# USB_Serial_Quad.net
KiCad netlist of a schematic drawn in Altium Designer
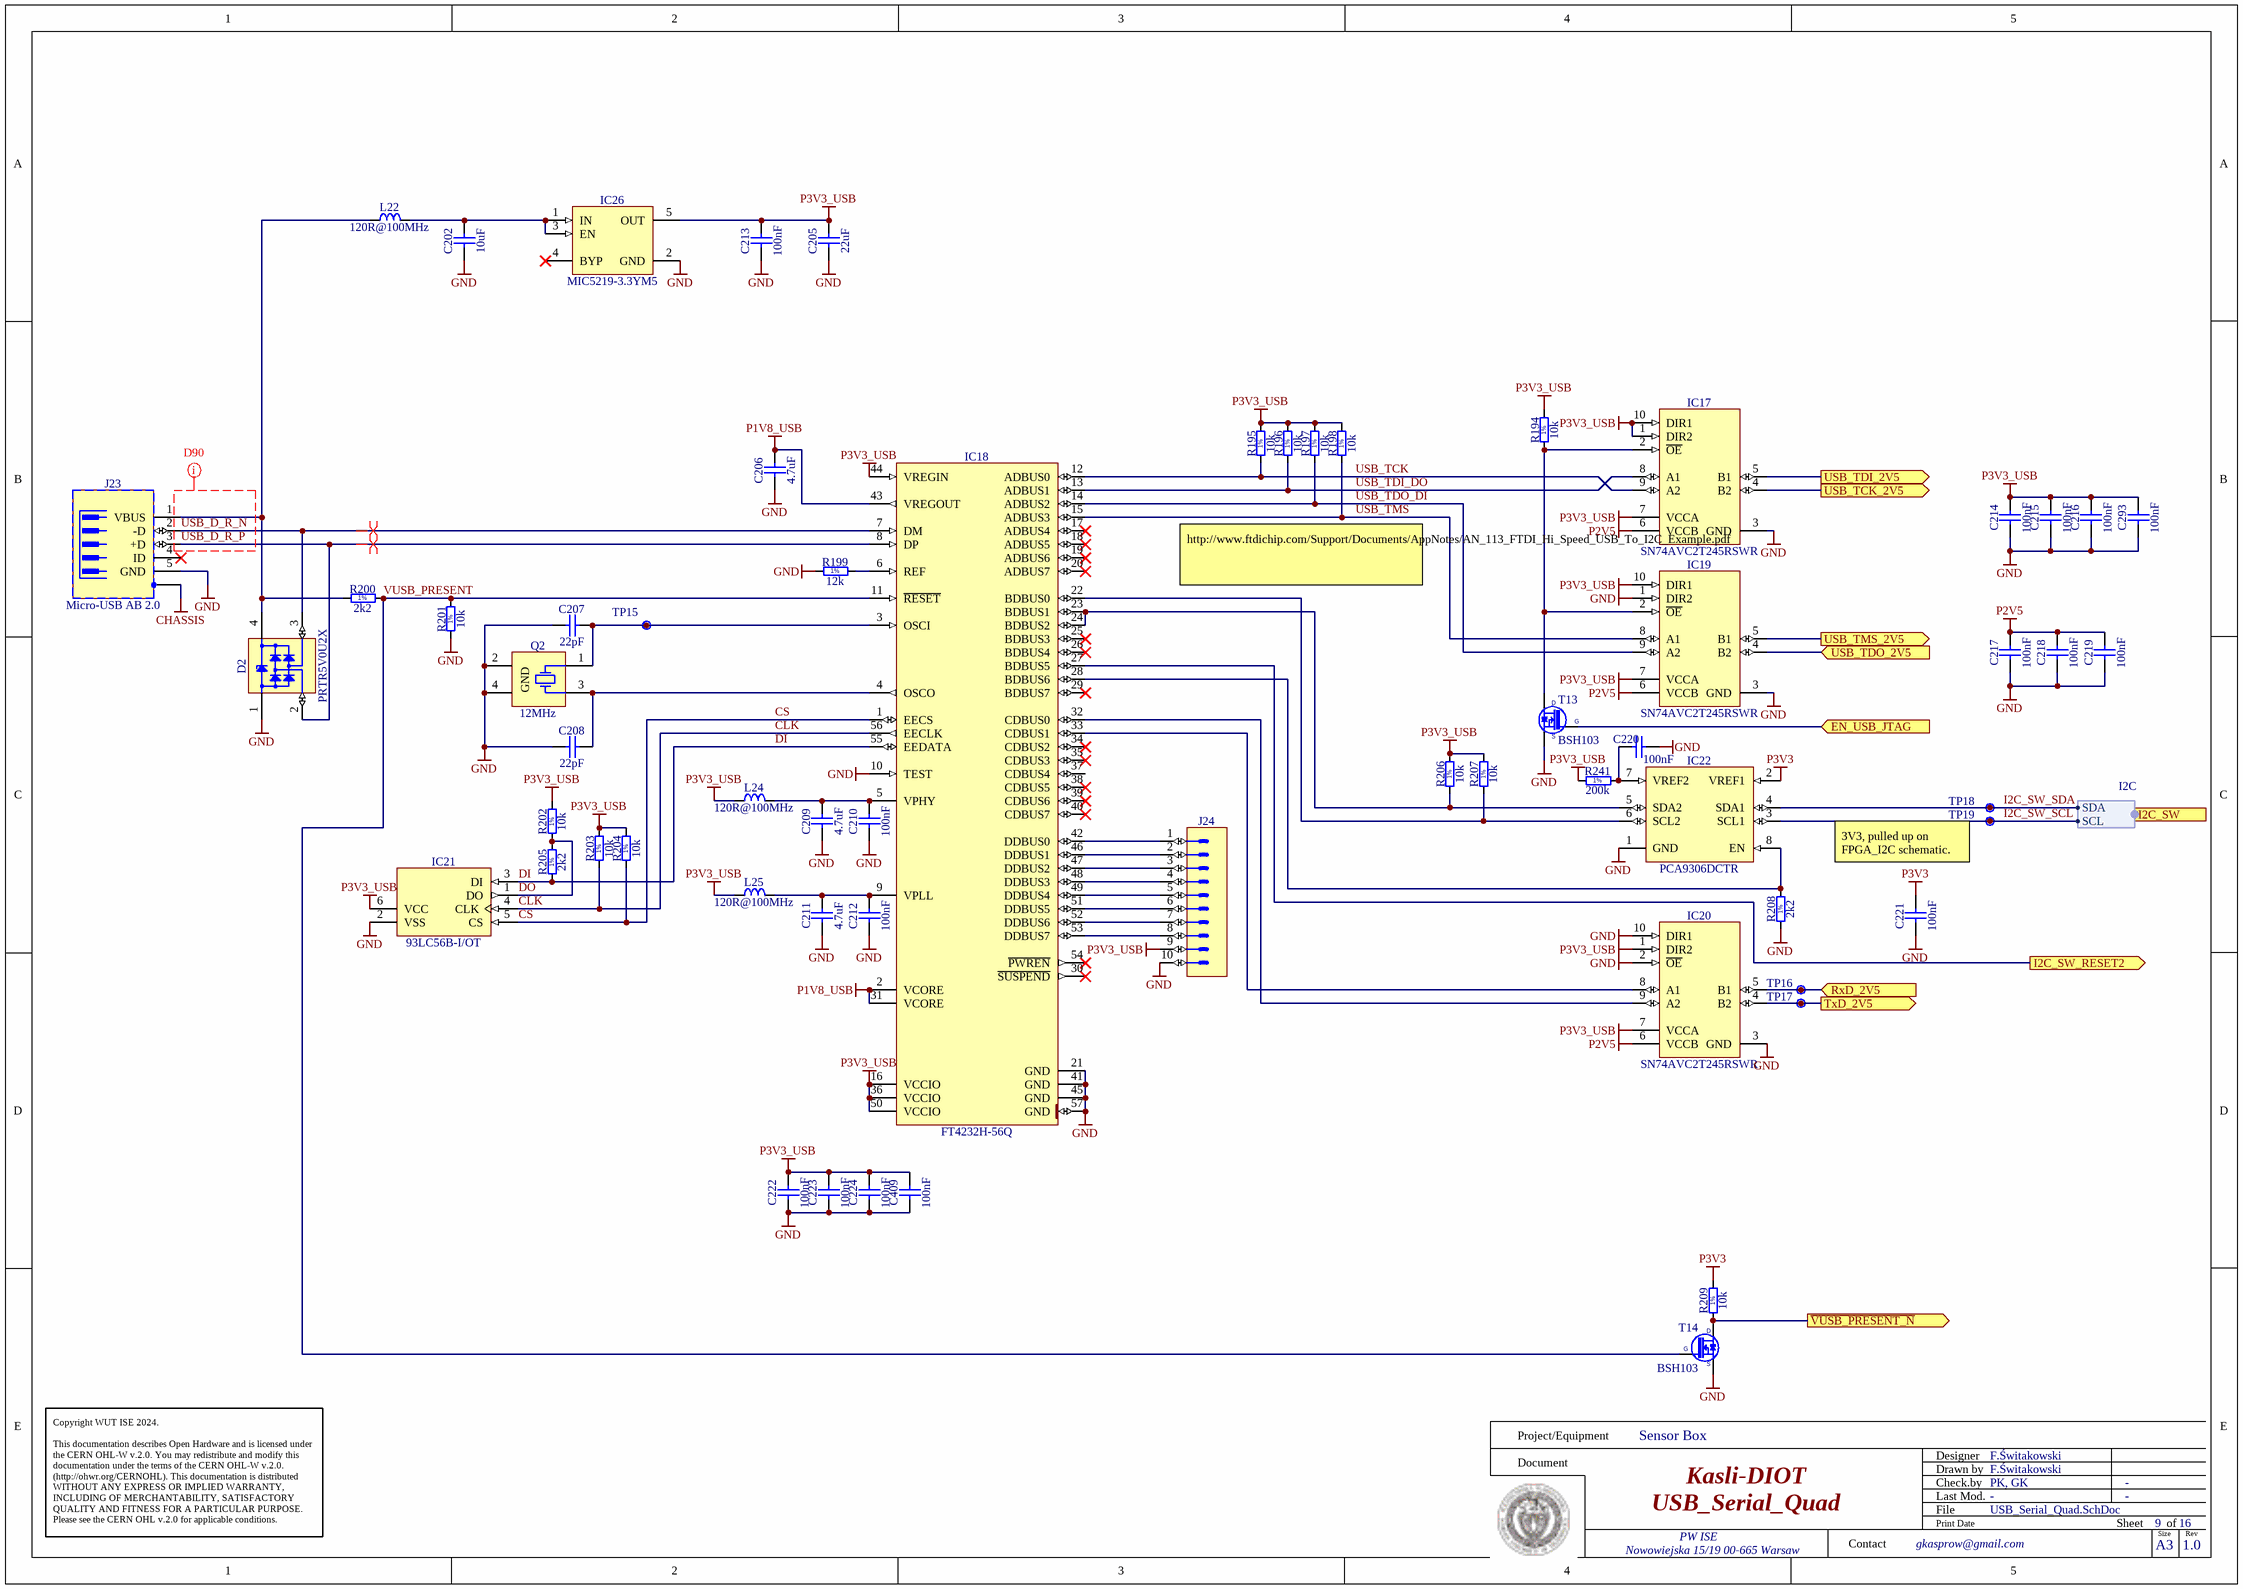
[diagram p0: USB_Serial_Quad.SchDoc]

(export (version "E")
  (design (tool "Eeschema 10.0.6"))
  (components
    (comp (ref "C202")
      (value "10uF")
      (footprint "CAPC1608X87N")
      (description "Non-polarised capacitor")
      (fields
        (field (name "PART NUMBER") "CC0603_10UF_6.3V_20%_X5R")
        (field (name "VOLTAGE") "6.3V")
        (field (name "AUTHOR") "CERN DEM JLC")
      )
      (libsource (lib "Capacitors") (part "Capacitor - non polarized"))
    )
    (comp (ref "C205")
      (value "22uF")
      (footprint "CAPC1709X100N")
      (description "Non-polarised capacitor")
      (fields
        (field (name "PART NUMBER") "CC0603_22UF_6.3V_20%_X5R")
        (field (name "VOLTAGE") "6.3V")
        (field (name "AUTHOR") "CERN DEM JLC")
      )
      (libsource (lib "Capacitors") (part "Capacitor - non polarized"))
    )
    (comp (ref "C206")
      (value "4.7uF")
      (footprint "CAPC2012X135N")
      (description "Non-polarised capacitor")
      (fields
        (field (name "PART NUMBER") "CC0805_4.7UF_10V_10%_X5R")
        (field (name "VOLTAGE") "10V")
        (field (name "AUTHOR") "CERN DEM JLC")
      )
      (libsource (lib "Capacitors") (part "Capacitor - non polarized"))
    )
    (comp (ref "C207")
      (value "22pF")
      (footprint "CAPC1005X55N")
      (description "Non-polarised capacitor")
      (fields
        (field (name "PART NUMBER") "CC0402_22PF_50V_5%_C0G")
        (field (name "VOLTAGE") "50V")
        (field (name "AUTHOR") "CERN DEM JLC")
      )
      (libsource (lib "Capacitors") (part "Capacitor - non polarized"))
    )
    (comp (ref "C208")
      (value "22pF")
      (footprint "CAPC1005X55N")
      (description "Non-polarised capacitor")
      (fields
        (field (name "PART NUMBER") "CC0402_22PF_50V_5%_C0G")
        (field (name "VOLTAGE") "50V")
        (field (name "AUTHOR") "CERN DEM JLC")
      )
      (libsource (lib "Capacitors") (part "Capacitor - non polarized"))
    )
    (comp (ref "C209")
      (value "4.7uF")
      (footprint "CAPC2012X135N")
      (description "Non-polarised capacitor")
      (fields
        (field (name "PART NUMBER") "CC0805_4.7UF_10V_10%_X5R")
        (field (name "VOLTAGE") "10V")
        (field (name "AUTHOR") "CERN DEM JLC")
      )
      (libsource (lib "Capacitors") (part "Capacitor - non polarized"))
    )
    (comp (ref "C210")
      (value "100nF")
      (footprint "CAPC0603X33N")
      (description "Non-polarised capacitor")
      (fields
        (field (name "PART NUMBER") "CC0201_100NF_6.3V_10%_X5R")
        (field (name "VOLTAGE") "6.3V")
        (field (name "AUTHOR") "CERN DEM JLC")
      )
      (libsource (lib "Capacitors") (part "Capacitor - non polarized"))
    )
    (comp (ref "C211")
      (value "4.7uF")
      (footprint "CAPC2012X135N")
      (description "Non-polarised capacitor")
      (fields
        (field (name "PART NUMBER") "CC0805_4.7UF_10V_10%_X5R")
        (field (name "VOLTAGE") "10V")
        (field (name "AUTHOR") "CERN DEM JLC")
      )
      (libsource (lib "Capacitors") (part "Capacitor - non polarized"))
    )
    (comp (ref "C212")
      (value "100nF")
      (footprint "CAPC0603X33N")
      (description "Non-polarised capacitor")
      (fields
        (field (name "PART NUMBER") "CC0201_100NF_6.3V_10%_X5R")
        (field (name "VOLTAGE") "6.3V")
        (field (name "AUTHOR") "CERN DEM JLC")
      )
      (libsource (lib "Capacitors") (part "Capacitor - non polarized"))
    )
    (comp (ref "C213")
      (value "100nF")
      (footprint "CAPC1005X55N")
      (description "Non-polarised capacitor")
      (fields
        (field (name "PART NUMBER") "CC0402_100NF_16V_10%_X7R")
        (field (name "VOLTAGE") "16V")
        (field (name "AUTHOR") "CERN DEM JLC")
      )
      (libsource (lib "Capacitors") (part "Capacitor - non polarized"))
    )
    (comp (ref "C214")
      (value "100nF")
      (footprint "CAPC1005X55N")
      (description "Non-polarised capacitor")
      (fields
        (field (name "PART NUMBER") "CC0402_100NF_16V_10%_X7R")
        (field (name "VOLTAGE") "16V")
        (field (name "AUTHOR") "CERN DEM JLC")
      )
      (libsource (lib "Capacitors") (part "Capacitor - non polarized"))
    )
    (comp (ref "C215")
      (value "100nF")
      (footprint "CAPC1005X55N")
      (description "Non-polarised capacitor")
      (fields
        (field (name "PART NUMBER") "CC0402_100NF_16V_10%_X7R")
        (field (name "VOLTAGE") "16V")
        (field (name "AUTHOR") "CERN DEM JLC")
      )
      (libsource (lib "Capacitors") (part "Capacitor - non polarized"))
    )
    (comp (ref "C216")
      (value "100nF")
      (footprint "CAPC1005X55N")
      (description "Non-polarised capacitor")
      (fields
        (field (name "PART NUMBER") "CC0402_100NF_16V_10%_X7R")
        (field (name "VOLTAGE") "16V")
        (field (name "AUTHOR") "CERN DEM JLC")
      )
      (libsource (lib "Capacitors") (part "Capacitor - non polarized"))
    )
    (comp (ref "C217")
      (value "100nF")
      (footprint "CAPC1005X55N")
      (description "Non-polarised capacitor")
      (fields
        (field (name "PART NUMBER") "CC0402_100NF_16V_10%_X7R")
        (field (name "VOLTAGE") "16V")
        (field (name "AUTHOR") "CERN DEM JLC")
      )
      (libsource (lib "Capacitors") (part "Capacitor - non polarized"))
    )
    (comp (ref "C218")
      (value "100nF")
      (footprint "CAPC1005X55N")
      (description "Non-polarised capacitor")
      (fields
        (field (name "PART NUMBER") "CC0402_100NF_16V_10%_X7R")
        (field (name "VOLTAGE") "16V")
        (field (name "AUTHOR") "CERN DEM JLC")
      )
      (libsource (lib "Capacitors") (part "Capacitor - non polarized"))
    )
    (comp (ref "C219")
      (value "100nF")
      (footprint "CAPC1005X55N")
      (description "Non-polarised capacitor")
      (fields
        (field (name "PART NUMBER") "CC0402_100NF_16V_10%_X7R")
        (field (name "VOLTAGE") "16V")
        (field (name "AUTHOR") "CERN DEM JLC")
      )
      (libsource (lib "Capacitors") (part "Capacitor - non polarized"))
    )
    (comp (ref "C220")
      (value "100nF")
      (footprint "CAPC1005X55N")
      (description "Non-polarised capacitor")
      (fields
        (field (name "PART NUMBER") "CC0402_100NF_16V_10%_X7R")
        (field (name "VOLTAGE") "16V")
        (field (name "AUTHOR") "CERN DEM JLC")
      )
      (libsource (lib "Capacitors") (part "Capacitor - non polarized"))
    )
    (comp (ref "C221")
      (value "100nF")
      (footprint "CAPC1005X55N")
      (description "Non-polarised capacitor")
      (fields
        (field (name "PART NUMBER") "CC0402_100NF_16V_10%_X7R")
        (field (name "VOLTAGE") "16V")
        (field (name "AUTHOR") "CERN DEM JLC")
      )
      (libsource (lib "Capacitors") (part "Capacitor - non polarized"))
    )
    (comp (ref "C222")
      (value "100nF")
      (footprint "CAPC1005X55N")
      (description "Non-polarised capacitor")
      (fields
        (field (name "PART NUMBER") "CC0402_100NF_16V_10%_X7R")
        (field (name "VOLTAGE") "16V")
        (field (name "AUTHOR") "CERN DEM JLC")
      )
      (libsource (lib "Capacitors") (part "Capacitor - non polarized"))
    )
    (comp (ref "C223")
      (value "100nF")
      (footprint "CAPC1005X55N")
      (description "Non-polarised capacitor")
      (fields
        (field (name "PART NUMBER") "CC0402_100NF_16V_10%_X7R")
        (field (name "VOLTAGE") "16V")
        (field (name "AUTHOR") "CERN DEM JLC")
      )
      (libsource (lib "Capacitors") (part "Capacitor - non polarized"))
    )
    (comp (ref "C224")
      (value "100nF")
      (footprint "CAPC1005X55N")
      (description "Non-polarised capacitor")
      (fields
        (field (name "PART NUMBER") "CC0402_100NF_16V_10%_X7R")
        (field (name "VOLTAGE") "16V")
        (field (name "AUTHOR") "CERN DEM JLC")
      )
      (libsource (lib "Capacitors") (part "Capacitor - non polarized"))
    )
    (comp (ref "C293")
      (value "100nF")
      (footprint "CAPC1005X55N")
      (description "Non-polarised capacitor")
      (fields
        (field (name "PART NUMBER") "CC0402_100NF_16V_10%_X7R")
        (field (name "VOLTAGE") "16V")
        (field (name "AUTHOR") "CERN DEM JLC")
      )
      (libsource (lib "Capacitors") (part "Capacitor - non polarized"))
    )
    (comp (ref "C409")
      (value "100nF")
      (footprint "CAPC1005X55N")
      (description "Non-polarised capacitor")
      (fields
        (field (name "PART NUMBER") "CC0402_100NF_16V_10%_X7R")
        (field (name "VOLTAGE") "16V")
        (field (name "AUTHOR") "CERN DEM JLC")
      )
      (libsource (lib "Capacitors") (part "Capacitor - non polarized"))
    )
    (comp (ref "D2")
      (value "PRTR5V0U2X")
      (footprint "SOT190P230X110-4N")
      (description "Ultra Low Capacitance Double Rail-to-Rail ESD Protection Diode")
      (fields
        (field (name "VOLTAGE") "5.5V")
        (field (name "MANUFACTURER") "NXP SEMICONDUCTORS")
        (field (name "AUTHOR") "CERN DEM JLC")
      )
      (libsource (lib "ICs And Semiconductors") (part "PRTR5V0U2X"))
    )
    (comp (ref "IC17")
      (value "SN74AVC2T245RSWR")
      (footprint "QFN40P140X180X55-10N")
      (description "Dual-Bit Dual-Supply Bus Transceiver With Configurable Voltage Translation and 3-State Outputs")
      (fields (field (name "MANUFACTURER") "TEXAS INSTRUMENTS") (field (name "AUTHOR") "CERN DEM JLC"))
      (libsource (lib "ICs And Semiconductors") (part "742T245"))
    )
    (comp (ref "IC18")
      (value "FT4232H-56Q")
      (footprint "QFN50P800X800X100-57N-S620")
      (description "Quad High Speed USB to Multipurpose UART/MPSSE IC")
      (fields
        (field (name "MANUFACTURER") "FUTURE TECHNOLOGY DEVICES INTERNATIONAL (FTDI)")
        (field (name "AUTHOR") "CERN DEM JLC")
      )
      (libsource (lib "ICs And Semiconductors") (part "FT4232H-56Q"))
    )
    (comp (ref "IC19")
      (value "SN74AVC2T245RSWR")
      (footprint "QFN40P140X180X55-10N")
      (description "Dual-Bit Dual-Supply Bus Transceiver With Configurable Voltage Translation and 3-State Outputs")
      (fields (field (name "MANUFACTURER") "TEXAS INSTRUMENTS") (field (name "AUTHOR") "CERN DEM JLC"))
      (libsource (lib "ICs And Semiconductors") (part "742T245"))
    )
    (comp (ref "IC20")
      (value "SN74AVC2T245RSWR")
      (footprint "QFN40P140X180X55-10N")
      (description "Dual-Bit Dual-Supply Bus Transceiver With Configurable Voltage Translation and 3-State Outputs")
      (fields (field (name "MANUFACTURER") "TEXAS INSTRUMENTS") (field (name "AUTHOR") "CERN DEM JLC"))
      (libsource (lib "ICs And Semiconductors") (part "742T245"))
    )
    (comp (ref "IC21")
      (value "93LC56B-I/OT")
      (footprint "SOT95P270X145-6N")
      (description "2K Microwire Compatible Serial EEPROM")
      (fields (field (name "MANUFACTURER") "MICROCHIP TECHNOLOGY") (field (name "AUTHOR") "CERN DEM BC"))
      (libsource (lib "ICs And Semiconductors") (part "93LC56B-I/OT"))
    )
    (comp (ref "IC22")
      (value "PCA9306DCTR")
      (footprint "SOP65P400X130-8N")
      (description "Dual Bidirectional I2C Bus And SMBus Voltage-Level Translator")
      (fields (field (name "MANUFACTURER") "TEXAS INSTRUMENTS") (field (name "AUTHOR") "CERN DEM JLC"))
      (libsource (lib "ICs And Semiconductors") (part "PCA9306D"))
    )
    (comp (ref "IC26")
      (value "MIC5219-3.3YM5")
      (footprint "SOT95P280X145-5N")
      (description "500mA Peak Output LDO Regulator")
      (fields (field (name "MANUFACTURER") "MICROCHIP TECHNOLOGY") (field (name "AUTHOR") "CERN DEM WB"))
      (libsource (lib "ICs And Semiconductors") (part "MIC5219-X.XYM5"))
    )
    (comp (ref "J23")
      (value "Micro-USB AB 2.0")
      (footprint "HIROSE_ZX62RD-AB-5P8")
      (description "5 Pin + 1 Shield USB Receptacle")
      (fields
        (field (name "PART NUMBER") "HIROSE_ZX62RD-AB-5P8")
        (field (name "MANUFACTURER") "HIROSE (HRS)")
        (field (name "AUTHOR") "CERN DEM JLC")
      )
      (libsource (lib "Connectors") (part "Connector USB 5 Pin + 1Shield"))
    )
    (comp (ref "J24")
      (value "Header 10")
      (footprint "SAMTEC_TSW-105-07-L-D-LL")
      (description "Connector 10 Male")
      (fields
        (field (name "PART NUMBER") "SAMTEC_TSW-105-07-L-D-LL")
        (field (name "MANUFACTURER") "SAMTEC")
        (field (name "AUTHOR") "CERN DEM JLC")
      )
      (libsource (lib "Connectors") (part "Connector 10 Male"))
    )
    (comp (ref "L22")
      (value "120R@100MHz")
      (footprint "INDC1608X65N")
      (description "Inductor")
      (fields
        (field (name "PART NUMBER") "IND0603_MURATA_BLM18SG121TN1D")
        (field (name "POWER") "3A")
        (field (name "AUTHOR") "CERN DEM JLC")
      )
      (libsource (lib "Inductors & Transformers") (part "Inductor"))
    )
    (comp (ref "L24")
      (value "120R@100MHz")
      (footprint "INDC1608X65N")
      (description "Inductor")
      (fields
        (field (name "PART NUMBER") "IND0603_MURATA_BLM18SG121TN1D")
        (field (name "POWER") "3A")
        (field (name "AUTHOR") "CERN DEM JLC")
      )
      (libsource (lib "Inductors & Transformers") (part "Inductor"))
    )
    (comp (ref "L25")
      (value "120R@100MHz")
      (footprint "INDC1608X65N")
      (description "Inductor")
      (fields
        (field (name "PART NUMBER") "IND0603_MURATA_BLM18SG121TN1D")
        (field (name "POWER") "3A")
        (field (name "AUTHOR") "CERN DEM JLC")
      )
      (libsource (lib "Inductors & Transformers") (part "Inductor"))
    )
    (comp (ref "Q2")
      (value "12MHz")
      (footprint "XTAL_TXC_7M")
      (description "Crystal 4 pins 1=XTAL Control 2=GND3=XTAL 4=GND")
      (fields
        (field (name "PART NUMBER") "XTAL_12MHZ_TXC_7M-12.000MAAJ-T")
        (field (name "MANUFACTURER") "TXC CORPORATION")
        (field (name "AUTHOR") "CERN DEM JLC")
      )
      (libsource (lib "ICs And Semiconductors") (part "Quartz Crystal 1X 2GND 3X 4GND"))
    )
    (comp (ref "R194")
      (value "10k")
      (footprint "RESC1005X40N")
      (description "Resistor - 1%")
      (fields
        (field (name "PART NUMBER") "R0402_10K_1%_0.0625W_100PPM")
        (field (name "POWER") "0.0625W")
        (field (name "AUTHOR") "CERN DEM JLC")
      )
      (libsource (lib "Resistors") (part "Resistor - 1%"))
    )
    (comp (ref "R195")
      (value "10k")
      (footprint "RESC1005X40N")
      (description "Resistor - 1%")
      (fields
        (field (name "PART NUMBER") "R0402_10K_1%_0.0625W_100PPM")
        (field (name "POWER") "0.0625W")
        (field (name "AUTHOR") "CERN DEM JLC")
      )
      (libsource (lib "Resistors") (part "Resistor - 1%"))
    )
    (comp (ref "R196")
      (value "10k")
      (footprint "RESC1005X40N")
      (description "Resistor - 1%")
      (fields
        (field (name "PART NUMBER") "R0402_10K_1%_0.0625W_100PPM")
        (field (name "POWER") "0.0625W")
        (field (name "AUTHOR") "CERN DEM JLC")
      )
      (libsource (lib "Resistors") (part "Resistor - 1%"))
    )
    (comp (ref "R197")
      (value "10k")
      (footprint "RESC1005X40N")
      (description "Resistor - 1%")
      (fields
        (field (name "PART NUMBER") "R0402_10K_1%_0.0625W_100PPM")
        (field (name "POWER") "0.0625W")
        (field (name "AUTHOR") "CERN DEM JLC")
      )
      (libsource (lib "Resistors") (part "Resistor - 1%"))
    )
    (comp (ref "R198")
      (value "10k")
      (footprint "RESC1005X40N")
      (description "Resistor - 1%")
      (fields
        (field (name "PART NUMBER") "R0402_10K_1%_0.0625W_100PPM")
        (field (name "POWER") "0.0625W")
        (field (name "AUTHOR") "CERN DEM JLC")
      )
      (libsource (lib "Resistors") (part "Resistor - 1%"))
    )
    (comp (ref "R199")
      (value "12k")
      (footprint "RESC1005X40N")
      (description "Resistor - 1%")
      (fields
        (field (name "PART NUMBER") "R0402_12K_1%_0.0625W_100PPM")
        (field (name "POWER") "0.0625W")
        (field (name "AUTHOR") "CERN DEM JLC")
      )
      (libsource (lib "Resistors") (part "Resistor - 1%"))
    )
    (comp (ref "R200")
      (value "2k2")
      (footprint "RESC1005X40N")
      (description "Resistor - 1%")
      (fields
        (field (name "PART NUMBER") "R0402_2K2_1%_0.0625W_100PPM")
        (field (name "POWER") "0.0625W")
        (field (name "AUTHOR") "CERN DEM JLC")
      )
      (libsource (lib "Resistors") (part "Resistor - 1%"))
    )
    (comp (ref "R201")
      (value "10k")
      (footprint "RESC1005X40N")
      (description "Resistor - 1%")
      (fields
        (field (name "PART NUMBER") "R0402_10K_1%_0.0625W_100PPM")
        (field (name "POWER") "0.0625W")
        (field (name "AUTHOR") "CERN DEM JLC")
      )
      (libsource (lib "Resistors") (part "Resistor - 1%"))
    )
    (comp (ref "R202")
      (value "10k")
      (footprint "RESC1005X40N")
      (description "Resistor - 1%")
      (fields
        (field (name "PART NUMBER") "R0402_10K_1%_0.0625W_100PPM")
        (field (name "POWER") "0.0625W")
        (field (name "AUTHOR") "CERN DEM JLC")
      )
      (libsource (lib "Resistors") (part "Resistor - 1%"))
    )
    (comp (ref "R203")
      (value "10k")
      (footprint "RESC1005X40N")
      (description "Resistor - 1%")
      (fields
        (field (name "PART NUMBER") "R0402_10K_1%_0.0625W_100PPM")
        (field (name "POWER") "0.0625W")
        (field (name "AUTHOR") "CERN DEM JLC")
      )
      (libsource (lib "Resistors") (part "Resistor - 1%"))
    )
    (comp (ref "R204")
      (value "10k")
      (footprint "RESC1005X40N")
      (description "Resistor - 1%")
      (fields
        (field (name "PART NUMBER") "R0402_10K_1%_0.0625W_100PPM")
        (field (name "POWER") "0.0625W")
        (field (name "AUTHOR") "CERN DEM JLC")
      )
      (libsource (lib "Resistors") (part "Resistor - 1%"))
    )
    (comp (ref "R205")
      (value "2k2")
      (footprint "RESC1005X40N")
      (description "Resistor - 1%")
      (fields
        (field (name "PART NUMBER") "R0402_2K2_1%_0.0625W_100PPM")
        (field (name "POWER") "0.0625W")
        (field (name "AUTHOR") "CERN DEM JLC")
      )
      (libsource (lib "Resistors") (part "Resistor - 1%"))
    )
    (comp (ref "R206")
      (value "10k")
      (footprint "RESC1005X40N")
      (description "Resistor - 1%")
      (fields
        (field (name "PART NUMBER") "R0402_10K_1%_0.0625W_100PPM")
        (field (name "POWER") "0.0625W")
        (field (name "AUTHOR") "CERN DEM JLC")
      )
      (libsource (lib "Resistors") (part "Resistor - 1%"))
    )
    (comp (ref "R207")
      (value "10k")
      (footprint "RESC1005X40N")
      (description "Resistor - 1%")
      (fields
        (field (name "PART NUMBER") "R0402_10K_1%_0.0625W_100PPM")
        (field (name "POWER") "0.0625W")
        (field (name "AUTHOR") "CERN DEM JLC")
      )
      (libsource (lib "Resistors") (part "Resistor - 1%"))
    )
    (comp (ref "R208")
      (value "2k2")
      (footprint "RESC1005X40N")
      (description "Resistor - 1%")
      (fields
        (field (name "PART NUMBER") "R0402_2K2_1%_0.0625W_100PPM")
        (field (name "POWER") "0.0625W")
        (field (name "AUTHOR") "CERN DEM JLC")
      )
      (libsource (lib "Resistors") (part "Resistor - 1%"))
    )
    (comp (ref "R209")
      (value "10k")
      (footprint "RESC1005X40N")
      (description "Resistor - 1%")
      (fields
        (field (name "PART NUMBER") "R0402_10K_1%_0.0625W_100PPM")
        (field (name "POWER") "0.0625W")
        (field (name "AUTHOR") "CERN DEM JLC")
      )
      (libsource (lib "Resistors") (part "Resistor - 1%"))
    )
    (comp (ref "R241")
      (value "200k")
      (footprint "RESC1005X40N")
      (description "Resistor - 1%")
      (fields
        (field (name "PART NUMBER") "R0402_200K_1%_0.0625W_100PPM")
        (field (name "POWER") "0.0625W")
        (field (name "AUTHOR") "CERN DEM JLC")
      )
      (libsource (lib "Resistors") (part "Resistor - 1%"))
    )
    (comp (ref "T13")
      (value "BSH103")
      (footprint "SOT95P230X110-3N")
      (description "N-CHANNEL MOSFET WITH DIODE")
      (fields (field (name "MANUFACTURER") "NEXPERIA") (field (name "AUTHOR") "CERN DEM JLC"))
      (libsource (lib "") (part "N-MOSFET-D 1G 2S 3D_1"))
    )
    (comp (ref "T14")
      (value "BSH103")
      (footprint "SOT95P230X110-3N")
      (description "N-CHANNEL MOSFET WITH DIODE")
      (fields (field (name "MANUFACTURER") "NEXPERIA") (field (name "AUTHOR") "CERN DEM JLC"))
      (libsource (lib "ICs And Semiconductors") (part "N-MOSFET-D 1G 2S 3D"))
    )
    (comp (ref "TP15")
      (value "Test Point")
      (footprint "TPS127")
      (fields (field (name "PART NUMBER") "SMD_PAD_1.27X1.27MM") (field (name "AUTHOR") "CERN DEM JLC"))
      (libsource (lib "Eletro-mechanical") (part "Test Point"))
    )
    (comp (ref "TP16")
      (value "Test Point")
      (footprint "TPS127")
      (fields (field (name "PART NUMBER") "SMD_PAD_1.27X1.27MM") (field (name "AUTHOR") "CERN DEM JLC"))
      (libsource (lib "Eletro-mechanical") (part "Test Point"))
    )
    (comp (ref "TP17")
      (value "Test Point")
      (footprint "TPS127")
      (fields (field (name "PART NUMBER") "SMD_PAD_1.27X1.27MM") (field (name "AUTHOR") "CERN DEM JLC"))
      (libsource (lib "Eletro-mechanical") (part "Test Point"))
    )
    (comp (ref "TP18")
      (value "Test Point")
      (footprint "TPS127")
      (fields (field (name "PART NUMBER") "SMD_PAD_1.27X1.27MM") (field (name "AUTHOR") "CERN DEM JLC"))
      (libsource (lib "Eletro-mechanical") (part "Test Point"))
    )
    (comp (ref "TP19")
      (value "Test Point")
      (footprint "TPS127")
      (fields (field (name "PART NUMBER") "SMD_PAD_1.27X1.27MM") (field (name "AUTHOR") "CERN DEM JLC"))
      (libsource (lib "Eletro-mechanical") (part "Test Point"))
    )
  )
  (nets
    (net (code "2") (name "/CLK") (class "Default")
      (node (ref "IC18") (pin "56") (pinfunction "EECLK_56") (pintype "output"))
      (node (ref "IC21") (pin "4") (pinfunction "CLK_4") (pintype "input"))
      (node (ref "R203") (pin "1") (pinfunction "1_1") (pintype "passive"))
    )
    (net (code "3") (name "/CS") (class "Default")
      (node (ref "IC18") (pin "1") (pinfunction "EECS_1") (pintype "bidirectional"))
      (node (ref "IC21") (pin "5") (pinfunction "CS_5") (pintype "input"))
      (node (ref "R204") (pin "1") (pinfunction "1_1") (pintype "passive"))
    )
    (net (code "4") (name "/DI") (class "Default")
      (node (ref "IC18") (pin "55") (pinfunction "EEDATA_55") (pintype "bidirectional"))
      (node (ref "IC21") (pin "3") (pinfunction "DI_3") (pintype "input"))
      (node (ref "R205") (pin "2") (pinfunction "2_2") (pintype "passive"))
    )
    (net (code "5") (name "/DO") (class "Default")
      (node (ref "IC21") (pin "1") (pinfunction "DO_1") (pintype "output"))
      (node (ref "R202") (pin "1") (pinfunction "1_1") (pintype "passive"))
      (node (ref "R205") (pin "1") (pinfunction "1_1") (pintype "passive"))
    )
    (net (code "6") (name "/EN_USB_JTAG") (class "Default")
      (node (ref "T13") (pin "1") (pinfunction "G_1") (pintype "passive"))
    )
    (net (code "7") (name "/I2C_SW_RESET2") (class "Default")
      (node (ref "IC18") (pin "27") (pinfunction "BDBUS5_27") (pintype "bidirectional"))
    )
    (net (code "8") (name "/I2C_SW_SCL") (class "Default")
      (node (ref "IC22") (pin "3") (pinfunction "SCL1_3") (pintype "bidirectional"))
      (node (ref "TP19") (pin "1") (pinfunction "1_1") (pintype "bidirectional"))
    )
    (net (code "9") (name "/I2C_SW_SDA") (class "Default")
      (node (ref "IC22") (pin "4") (pinfunction "SDA1_4") (pintype "bidirectional"))
      (node (ref "TP18") (pin "1") (pinfunction "1_1") (pintype "bidirectional"))
    )
    (net (code "10") (name "/RxD_2V5") (class "Default")
      (node (ref "IC20") (pin "5") (pinfunction "B1_5") (pintype "bidirectional"))
      (node (ref "TP16") (pin "1") (pinfunction "1_1") (pintype "bidirectional"))
    )
    (net (code "11") (name "/TxD_2V5") (class "Default")
      (node (ref "IC20") (pin "4") (pinfunction "B2_4") (pintype "bidirectional"))
      (node (ref "TP17") (pin "1") (pinfunction "1_1") (pintype "bidirectional"))
    )
    (net (code "12") (name "/USB_D_R_N") (class "Default")
      (node (ref "D2") (pin "3") (pinfunction "I/O2_3") (pintype "bidirectional"))
      (node (ref "IC18") (pin "7") (pinfunction "DM_7") (pintype "input"))
      (node (ref "J23") (pin "2") (pinfunction "-D_2") (pintype "bidirectional"))
    )
    (net (code "13") (name "/USB_D_R_P") (class "Default")
      (node (ref "D2") (pin "2") (pinfunction "I/O1_2") (pintype "bidirectional"))
      (node (ref "IC18") (pin "8") (pinfunction "DP_8") (pintype "input"))
      (node (ref "J23") (pin "3") (pinfunction "+D_3") (pintype "bidirectional"))
    )
    (net (code "14") (name "/USB_TCK") (class "Default")
      (node (ref "IC17") (pin "9") (pinfunction "A2_9") (pintype "bidirectional"))
      (node (ref "IC18") (pin "12") (pinfunction "ADBUS0_12") (pintype "bidirectional"))
      (node (ref "R195") (pin "1") (pinfunction "1_1") (pintype "passive"))
    )
    (net (code "15") (name "/USB_TCK_2V5") (class "Default")
      (node (ref "IC17") (pin "4") (pinfunction "B2_4") (pintype "bidirectional"))
    )
    (net (code "16") (name "/USB_TDI_2V5") (class "Default")
      (node (ref "IC17") (pin "5") (pinfunction "B1_5") (pintype "bidirectional"))
    )
    (net (code "17") (name "/USB_TDI_DO") (class "Default")
      (node (ref "IC17") (pin "8") (pinfunction "A1_8") (pintype "bidirectional"))
      (node (ref "IC18") (pin "13") (pinfunction "ADBUS1_13") (pintype "bidirectional"))
      (node (ref "R196") (pin "1") (pinfunction "1_1") (pintype "passive"))
    )
    (net (code "18") (name "/USB_TDO_2V5") (class "Default")
      (node (ref "IC19") (pin "4") (pinfunction "B2_4") (pintype "bidirectional"))
    )
    (net (code "19") (name "/USB_TDO_DI") (class "Default")
      (node (ref "IC18") (pin "14") (pinfunction "ADBUS2_14") (pintype "bidirectional"))
      (node (ref "IC19") (pin "9") (pinfunction "A2_9") (pintype "bidirectional"))
      (node (ref "R197") (pin "1") (pinfunction "1_1") (pintype "passive"))
    )
    (net (code "20") (name "/USB_TMS") (class "Default")
      (node (ref "IC18") (pin "15") (pinfunction "ADBUS3_15") (pintype "bidirectional"))
      (node (ref "IC19") (pin "8") (pinfunction "A1_8") (pintype "bidirectional"))
      (node (ref "R198") (pin "1") (pinfunction "1_1") (pintype "passive"))
    )
    (net (code "21") (name "/USB_TMS_2V5") (class "Default")
      (node (ref "IC19") (pin "5") (pinfunction "B1_5") (pintype "bidirectional"))
    )
    (net (code "22") (name "/VUSB_PRESENT") (class "Default")
      (node (ref "IC18") (pin "11") (pinfunction "~{RESET}_11") (pintype "input"))
      (node (ref "R200") (pin "2") (pinfunction "2_2") (pintype "passive"))
      (node (ref "R201") (pin "2") (pinfunction "2_2") (pintype "passive"))
      (node (ref "T14") (pin "1") (pinfunction "G_1") (pintype "passive"))
    )
    (net (code "23") (name "/VUSB_PRESENT_N") (class "Default")
      (node (ref "R209") (pin "1") (pinfunction "1_1") (pintype "passive"))
      (node (ref "T14") (pin "3") (pinfunction "D_3") (pintype "passive"))
    )
    (net (code "25") (name "CHASSIS") (class "Default")
      (node (ref "J23") (pin "6") (pinfunction "SH_6") (pintype "power_in"))
    )
    (net (code "26") (name "GND") (class "Default")
      (node (ref "C202") (pin "1") (pinfunction "1_1") (pintype "passive"))
      (node (ref "C205") (pin "1") (pinfunction "1_1") (pintype "passive"))
      (node (ref "C206") (pin "1") (pinfunction "1_1") (pintype "passive"))
      (node (ref "C207") (pin "1") (pinfunction "1_1") (pintype "passive"))
      (node (ref "C208") (pin "1") (pinfunction "1_1") (pintype "passive"))
      (node (ref "C209") (pin "1") (pinfunction "1_1") (pintype "passive"))
      (node (ref "C210") (pin "1") (pinfunction "1_1") (pintype "passive"))
      (node (ref "C211") (pin "1") (pinfunction "1_1") (pintype "passive"))
      (node (ref "C212") (pin "1") (pinfunction "1_1") (pintype "passive"))
      (node (ref "C213") (pin "1") (pinfunction "1_1") (pintype "passive"))
      (node (ref "C214") (pin "1") (pinfunction "1_1") (pintype "passive"))
      (node (ref "C215") (pin "1") (pinfunction "1_1") (pintype "passive"))
      (node (ref "C216") (pin "1") (pinfunction "1_1") (pintype "passive"))
      (node (ref "C217") (pin "1") (pinfunction "1_1") (pintype "passive"))
      (node (ref "C218") (pin "1") (pinfunction "1_1") (pintype "passive"))
      (node (ref "C219") (pin "1") (pinfunction "1_1") (pintype "passive"))
      (node (ref "C220") (pin "2") (pinfunction "2_2") (pintype "passive"))
      (node (ref "C221") (pin "1") (pinfunction "1_1") (pintype "passive"))
      (node (ref "C222") (pin "1") (pinfunction "1_1") (pintype "passive"))
      (node (ref "C223") (pin "1") (pinfunction "1_1") (pintype "passive"))
      (node (ref "C224") (pin "1") (pinfunction "1_1") (pintype "passive"))
      (node (ref "C293") (pin "1") (pinfunction "1_1") (pintype "passive"))
      (node (ref "C409") (pin "1") (pinfunction "1_1") (pintype "passive"))
      (node (ref "D2") (pin "1") (pinfunction "GND_1") (pintype "power_in"))
      (node (ref "IC17") (pin "3") (pinfunction "GND_3") (pintype "power_in"))
      (node (ref "IC18") (pin "10") (pinfunction "TEST_10") (pintype "input"))
      (node (ref "IC18") (pin "21") (pinfunction "GND_21") (pintype "power_in"))
      (node (ref "IC18") (pin "41") (pinfunction "GND_41") (pintype "power_in"))
      (node (ref "IC18") (pin "45") (pinfunction "GND_45") (pintype "power_in"))
      (node (ref "IC18") (pin "57") (pinfunction "GND_57") (pintype "bidirectional"))
      (node (ref "IC19") (pin "1") (pinfunction "DIR2_1") (pintype "input"))
      (node (ref "IC19") (pin "3") (pinfunction "GND_3") (pintype "power_in"))
      (node (ref "IC20") (pin "10") (pinfunction "DIR1_10") (pintype "input"))
      (node (ref "IC20") (pin "2") (pinfunction "~{OE}_2") (pintype "input"))
      (node (ref "IC20") (pin "3") (pinfunction "GND_3") (pintype "power_in"))
      (node (ref "IC21") (pin "2") (pinfunction "VSS_2") (pintype "power_in"))
      (node (ref "IC22") (pin "1") (pinfunction "GND_1") (pintype "power_in"))
      (node (ref "IC26") (pin "2") (pinfunction "GND_2") (pintype "power_in"))
      (node (ref "J23") (pin "5") (pinfunction "GND_5") (pintype "power_in"))
      (node (ref "J24") (pin "10") (pinfunction "10_10") (pintype "bidirectional"))
      (node (ref "Q2") (pin "2") (pinfunction "GND_2") (pintype "power_in"))
      (node (ref "Q2") (pin "4") (pinfunction "GND_4") (pintype "power_in"))
      (node (ref "R199") (pin "1") (pinfunction "1_1") (pintype "passive"))
      (node (ref "R201") (pin "1") (pinfunction "1_1") (pintype "passive"))
      (node (ref "R208") (pin "1") (pinfunction "1_1") (pintype "passive"))
      (node (ref "T13") (pin "2") (pinfunction "S_2") (pintype "passive"))
      (node (ref "T14") (pin "2") (pinfunction "S_2") (pintype "passive"))
    )
    (net (code "27") (name "Net-(D2-VCC)") (class "Default")
      (node (ref "D2") (pin "4") (pinfunction "VCC_4") (pintype "power_in"))
      (node (ref "J23") (pin "1") (pinfunction "VBUS_1") (pintype "power_in"))
      (node (ref "L22") (pin "1") (pinfunction "1_1") (pintype "passive"))
      (node (ref "R200") (pin "1") (pinfunction "1_1") (pintype "passive"))
    )
    (net (code "28") (name "Net-(IC17-~{OE})") (class "Default")
      (node (ref "IC17") (pin "2") (pinfunction "~{OE}_2") (pintype "input"))
      (node (ref "IC19") (pin "2") (pinfunction "~{OE}_2") (pintype "input"))
      (node (ref "R194") (pin "1") (pinfunction "1_1") (pintype "passive"))
      (node (ref "T13") (pin "3") (pinfunction "D_3") (pintype "passive"))
    )
    (net (code "29") (name "Net-(IC18-BDBUS0)") (class "Default")
      (node (ref "IC18") (pin "22") (pinfunction "BDBUS0_22") (pintype "bidirectional"))
      (node (ref "IC22") (pin "6") (pinfunction "SCL2_6") (pintype "bidirectional"))
      (node (ref "R207") (pin "1") (pinfunction "1_1") (pintype "passive"))
    )
    (net (code "30") (name "Net-(IC18-BDBUS1)") (class "Default")
      (node (ref "IC18") (pin "23") (pinfunction "BDBUS1_23") (pintype "bidirectional"))
      (node (ref "IC18") (pin "24") (pinfunction "BDBUS2_24") (pintype "bidirectional"))
      (node (ref "IC22") (pin "5") (pinfunction "SDA2_5") (pintype "bidirectional"))
      (node (ref "R206") (pin "1") (pinfunction "1_1") (pintype "passive"))
    )
    (net (code "31") (name "Net-(IC18-BDBUS6)") (class "Default")
      (node (ref "IC18") (pin "28") (pinfunction "BDBUS6_28") (pintype "bidirectional"))
      (node (ref "IC22") (pin "8") (pinfunction "EN_8") (pintype "input"))
      (node (ref "R208") (pin "2") (pinfunction "2_2") (pintype "passive"))
    )
    (net (code "32") (name "Net-(IC18-CDBUS0)") (class "Default")
      (node (ref "IC18") (pin "32") (pinfunction "CDBUS0_32") (pintype "bidirectional"))
      (node (ref "IC20") (pin "9") (pinfunction "A2_9") (pintype "bidirectional"))
    )
    (net (code "33") (name "Net-(IC18-CDBUS1)") (class "Default")
      (node (ref "IC18") (pin "33") (pinfunction "CDBUS1_33") (pintype "bidirectional"))
      (node (ref "IC20") (pin "8") (pinfunction "A1_8") (pintype "bidirectional"))
    )
    (net (code "34") (name "Net-(IC18-DDBUS0)") (class "Default")
      (node (ref "IC18") (pin "42") (pinfunction "DDBUS0_42") (pintype "bidirectional"))
      (node (ref "J24") (pin "1") (pinfunction "1_1") (pintype "bidirectional"))
    )
    (net (code "35") (name "Net-(IC18-DDBUS1)") (class "Default")
      (node (ref "IC18") (pin "46") (pinfunction "DDBUS1_46") (pintype "bidirectional"))
      (node (ref "J24") (pin "2") (pinfunction "2_2") (pintype "bidirectional"))
    )
    (net (code "36") (name "Net-(IC18-DDBUS2)") (class "Default")
      (node (ref "IC18") (pin "47") (pinfunction "DDBUS2_47") (pintype "bidirectional"))
      (node (ref "J24") (pin "3") (pinfunction "3_3") (pintype "bidirectional"))
    )
    (net (code "37") (name "Net-(IC18-DDBUS3)") (class "Default")
      (node (ref "IC18") (pin "48") (pinfunction "DDBUS3_48") (pintype "bidirectional"))
      (node (ref "J24") (pin "4") (pinfunction "4_4") (pintype "bidirectional"))
    )
    (net (code "38") (name "Net-(IC18-DDBUS4)") (class "Default")
      (node (ref "IC18") (pin "49") (pinfunction "DDBUS4_49") (pintype "bidirectional"))
      (node (ref "J24") (pin "5") (pinfunction "5_5") (pintype "bidirectional"))
    )
    (net (code "39") (name "Net-(IC18-DDBUS5)") (class "Default")
      (node (ref "IC18") (pin "51") (pinfunction "DDBUS5_51") (pintype "bidirectional"))
      (node (ref "J24") (pin "6") (pinfunction "6_6") (pintype "bidirectional"))
    )
    (net (code "40") (name "Net-(IC18-DDBUS6)") (class "Default")
      (node (ref "IC18") (pin "52") (pinfunction "DDBUS6_52") (pintype "bidirectional"))
      (node (ref "J24") (pin "7") (pinfunction "7_7") (pintype "bidirectional"))
    )
    (net (code "41") (name "Net-(IC18-DDBUS7)") (class "Default")
      (node (ref "IC18") (pin "53") (pinfunction "DDBUS7_53") (pintype "bidirectional"))
      (node (ref "J24") (pin "8") (pinfunction "8_8") (pintype "bidirectional"))
    )
    (net (code "42") (name "Net-(IC18-OSCI)") (class "Default")
      (node (ref "C207") (pin "2") (pinfunction "2_2") (pintype "passive"))
      (node (ref "IC18") (pin "3") (pinfunction "OSCI_3") (pintype "input"))
      (node (ref "Q2") (pin "1") (pinfunction "X_1") (pintype "passive"))
      (node (ref "TP15") (pin "1") (pinfunction "1_1") (pintype "bidirectional"))
    )
    (net (code "43") (name "Net-(IC18-OSCO)") (class "Default")
      (node (ref "C208") (pin "2") (pinfunction "2_2") (pintype "passive"))
      (node (ref "IC18") (pin "4") (pinfunction "OSCO_4") (pintype "output"))
      (node (ref "Q2") (pin "3") (pinfunction "X_3") (pintype "passive"))
    )
    (net (code "44") (name "Net-(IC18-REF)") (class "Default")
      (node (ref "IC18") (pin "6") (pinfunction "REF_6") (pintype "input"))
      (node (ref "R199") (pin "2") (pinfunction "2_2") (pintype "passive"))
    )
    (net (code "45") (name "Net-(IC18-VPHY)") (class "Default")
      (node (ref "C209") (pin "2") (pinfunction "2_2") (pintype "passive"))
      (node (ref "C210") (pin "2") (pinfunction "2_2") (pintype "passive"))
      (node (ref "IC18") (pin "5") (pinfunction "VPHY_5") (pintype "power_in"))
      (node (ref "L24") (pin "2") (pinfunction "2_2") (pintype "passive"))
    )
    (net (code "46") (name "Net-(IC18-VPLL)") (class "Default")
      (node (ref "C211") (pin "2") (pinfunction "2_2") (pintype "passive"))
      (node (ref "C212") (pin "2") (pinfunction "2_2") (pintype "passive"))
      (node (ref "IC18") (pin "9") (pinfunction "VPLL_9") (pintype "power_in"))
      (node (ref "L25") (pin "2") (pinfunction "2_2") (pintype "passive"))
    )
    (net (code "47") (name "Net-(IC22-VREF2)") (class "Default")
      (node (ref "C220") (pin "1") (pinfunction "1_1") (pintype "passive"))
      (node (ref "IC22") (pin "7") (pinfunction "VREF2_7") (pintype "input"))
      (node (ref "R241") (pin "2") (pinfunction "2_2") (pintype "passive"))
    )
    (net (code "48") (name "Net-(IC26-EN)") (class "Default")
      (node (ref "C202") (pin "2") (pinfunction "2_2") (pintype "passive"))
      (node (ref "IC26") (pin "1") (pinfunction "IN_1") (pintype "input"))
      (node (ref "IC26") (pin "3") (pinfunction "EN_3") (pintype "input"))
      (node (ref "L22") (pin "2") (pinfunction "2_2") (pintype "passive"))
    )
    (net (code "49") (name "P1V8_USB") (class "Default")
      (node (ref "C206") (pin "2") (pinfunction "2_2") (pintype "passive"))
      (node (ref "IC18") (pin "2") (pinfunction "VCORE_2") (pintype "power_in"))
      (node (ref "IC18") (pin "31") (pinfunction "VCORE_31") (pintype "power_in"))
      (node (ref "IC18") (pin "43") (pinfunction "VREGOUT_43") (pintype "output"))
    )
    (net (code "50") (name "P2V5") (class "Default")
      (node (ref "C217") (pin "2") (pinfunction "2_2") (pintype "passive"))
      (node (ref "C218") (pin "2") (pinfunction "2_2") (pintype "passive"))
      (node (ref "C219") (pin "2") (pinfunction "2_2") (pintype "passive"))
      (node (ref "IC17") (pin "6") (pinfunction "VCCB_6") (pintype "power_in"))
      (node (ref "IC19") (pin "6") (pinfunction "VCCB_6") (pintype "power_in"))
      (node (ref "IC20") (pin "6") (pinfunction "VCCB_6") (pintype "power_in"))
    )
    (net (code "51") (name "P3V3") (class "Default")
      (node (ref "C221") (pin "2") (pinfunction "2_2") (pintype "passive"))
      (node (ref "IC22") (pin "2") (pinfunction "VREF1_2") (pintype "input"))
      (node (ref "R209") (pin "2") (pinfunction "2_2") (pintype "passive"))
    )
    (net (code "52") (name "P3V3_USB") (class "Default")
      (node (ref "C205") (pin "2") (pinfunction "2_2") (pintype "passive"))
      (node (ref "C213") (pin "2") (pinfunction "2_2") (pintype "passive"))
      (node (ref "C214") (pin "2") (pinfunction "2_2") (pintype "passive"))
      (node (ref "C215") (pin "2") (pinfunction "2_2") (pintype "passive"))
      (node (ref "C216") (pin "2") (pinfunction "2_2") (pintype "passive"))
      (node (ref "C222") (pin "2") (pinfunction "2_2") (pintype "passive"))
      (node (ref "C223") (pin "2") (pinfunction "2_2") (pintype "passive"))
      (node (ref "C224") (pin "2") (pinfunction "2_2") (pintype "passive"))
      (node (ref "C293") (pin "2") (pinfunction "2_2") (pintype "passive"))
      (node (ref "C409") (pin "2") (pinfunction "2_2") (pintype "passive"))
      (node (ref "IC17") (pin "1") (pinfunction "DIR2_1") (pintype "input"))
      (node (ref "IC17") (pin "10") (pinfunction "DIR1_10") (pintype "input"))
      (node (ref "IC17") (pin "7") (pinfunction "VCCA_7") (pintype "power_in"))
      (node (ref "IC18") (pin "16") (pinfunction "VCCIO_16") (pintype "power_in"))
      (node (ref "IC18") (pin "36") (pinfunction "VCCIO_36") (pintype "power_in"))
      (node (ref "IC18") (pin "44") (pinfunction "VREGIN_44") (pintype "input"))
      (node (ref "IC18") (pin "50") (pinfunction "VCCIO_50") (pintype "power_in"))
      (node (ref "IC19") (pin "10") (pinfunction "DIR1_10") (pintype "input"))
      (node (ref "IC19") (pin "7") (pinfunction "VCCA_7") (pintype "power_in"))
      (node (ref "IC20") (pin "1") (pinfunction "DIR2_1") (pintype "input"))
      (node (ref "IC20") (pin "7") (pinfunction "VCCA_7") (pintype "power_in"))
      (node (ref "IC21") (pin "6") (pinfunction "VCC_6") (pintype "power_in"))
      (node (ref "IC26") (pin "5") (pinfunction "OUT_5") (pintype "power_in"))
      (node (ref "J24") (pin "9") (pinfunction "9_9") (pintype "bidirectional"))
      (node (ref "L24") (pin "1") (pinfunction "1_1") (pintype "passive"))
      (node (ref "L25") (pin "1") (pinfunction "1_1") (pintype "passive"))
      (node (ref "R194") (pin "2") (pinfunction "2_2") (pintype "passive"))
      (node (ref "R195") (pin "2") (pinfunction "2_2") (pintype "passive"))
      (node (ref "R196") (pin "2") (pinfunction "2_2") (pintype "passive"))
      (node (ref "R197") (pin "2") (pinfunction "2_2") (pintype "passive"))
      (node (ref "R198") (pin "2") (pinfunction "2_2") (pintype "passive"))
      (node (ref "R202") (pin "2") (pinfunction "2_2") (pintype "passive"))
      (node (ref "R203") (pin "2") (pinfunction "2_2") (pintype "passive"))
      (node (ref "R204") (pin "2") (pinfunction "2_2") (pintype "passive"))
      (node (ref "R206") (pin "2") (pinfunction "2_2") (pintype "passive"))
      (node (ref "R207") (pin "2") (pinfunction "2_2") (pintype "passive"))
      (node (ref "R241") (pin "1") (pinfunction "1_1") (pintype "passive"))
    )
    (net (code "53") (name "unconnected-(IC18-ADBUS4-Pad17)") (class "Default")
      (node (ref "IC18") (pin "17") (pinfunction "ADBUS4_17") (pintype "bidirectional+no_connect"))
    )
    (net (code "54") (name "unconnected-(IC18-ADBUS5-Pad18)") (class "Default")
      (node (ref "IC18") (pin "18") (pinfunction "ADBUS5_18") (pintype "bidirectional+no_connect"))
    )
    (net (code "55") (name "unconnected-(IC18-ADBUS6-Pad19)") (class "Default")
      (node (ref "IC18") (pin "19") (pinfunction "ADBUS6_19") (pintype "bidirectional+no_connect"))
    )
    (net (code "56") (name "unconnected-(IC18-ADBUS7-Pad20)") (class "Default")
      (node (ref "IC18") (pin "20") (pinfunction "ADBUS7_20") (pintype "bidirectional+no_connect"))
    )
    (net (code "57") (name "unconnected-(IC18-BDBUS3-Pad25)") (class "Default")
      (node (ref "IC18") (pin "25") (pinfunction "BDBUS3_25") (pintype "bidirectional+no_connect"))
    )
    (net (code "58") (name "unconnected-(IC18-BDBUS4-Pad26)") (class "Default")
      (node (ref "IC18") (pin "26") (pinfunction "BDBUS4_26") (pintype "bidirectional+no_connect"))
    )
    (net (code "59") (name "unconnected-(IC18-BDBUS7-Pad29)") (class "Default")
      (node (ref "IC18") (pin "29") (pinfunction "BDBUS7_29") (pintype "bidirectional+no_connect"))
    )
    (net (code "60") (name "unconnected-(IC18-CDBUS2-Pad34)") (class "Default")
      (node (ref "IC18") (pin "34") (pinfunction "CDBUS2_34") (pintype "bidirectional+no_connect"))
    )
    (net (code "61") (name "unconnected-(IC18-CDBUS3-Pad35)") (class "Default")
      (node (ref "IC18") (pin "35") (pinfunction "CDBUS3_35") (pintype "bidirectional+no_connect"))
    )
    (net (code "62") (name "unconnected-(IC18-CDBUS4-Pad37)") (class "Default")
      (node (ref "IC18") (pin "37") (pinfunction "CDBUS4_37") (pintype "bidirectional"))
    )
    (net (code "63") (name "unconnected-(IC18-CDBUS5-Pad38)") (class "Default")
      (node (ref "IC18") (pin "38") (pinfunction "CDBUS5_38") (pintype "bidirectional+no_connect"))
    )
    (net (code "64") (name "unconnected-(IC18-CDBUS6-Pad39)") (class "Default")
      (node (ref "IC18") (pin "39") (pinfunction "CDBUS6_39") (pintype "bidirectional+no_connect"))
    )
    (net (code "65") (name "unconnected-(IC18-CDBUS7-Pad40)") (class "Default")
      (node (ref "IC18") (pin "40") (pinfunction "CDBUS7_40") (pintype "bidirectional+no_connect"))
    )
    (net (code "66") (name "unconnected-(IC18-~{PWREN}-Pad54)") (class "Default")
      (node (ref "IC18") (pin "54") (pinfunction "~{PWREN}_54") (pintype "output+no_connect"))
    )
    (net (code "67") (name "unconnected-(IC18-~{SUSPEND}-Pad30)") (class "Default")
      (node (ref "IC18") (pin "30") (pinfunction "~{SUSPEND}_30") (pintype "output+no_connect"))
    )
    (net (code "68") (name "unconnected-(IC26-BYP-Pad4)") (class "Default")
      (node (ref "IC26") (pin "4") (pinfunction "BYP_4") (pintype "passive+no_connect"))
    )
    (net (code "69") (name "unconnected-(J23-ID-Pad4)") (class "Default")
      (node (ref "J23") (pin "4") (pinfunction "ID_4") (pintype "passive+no_connect"))
    )
  )
)
